# 01_Structure.net
KiCad netlist of a schematic drawn in Altium Designer
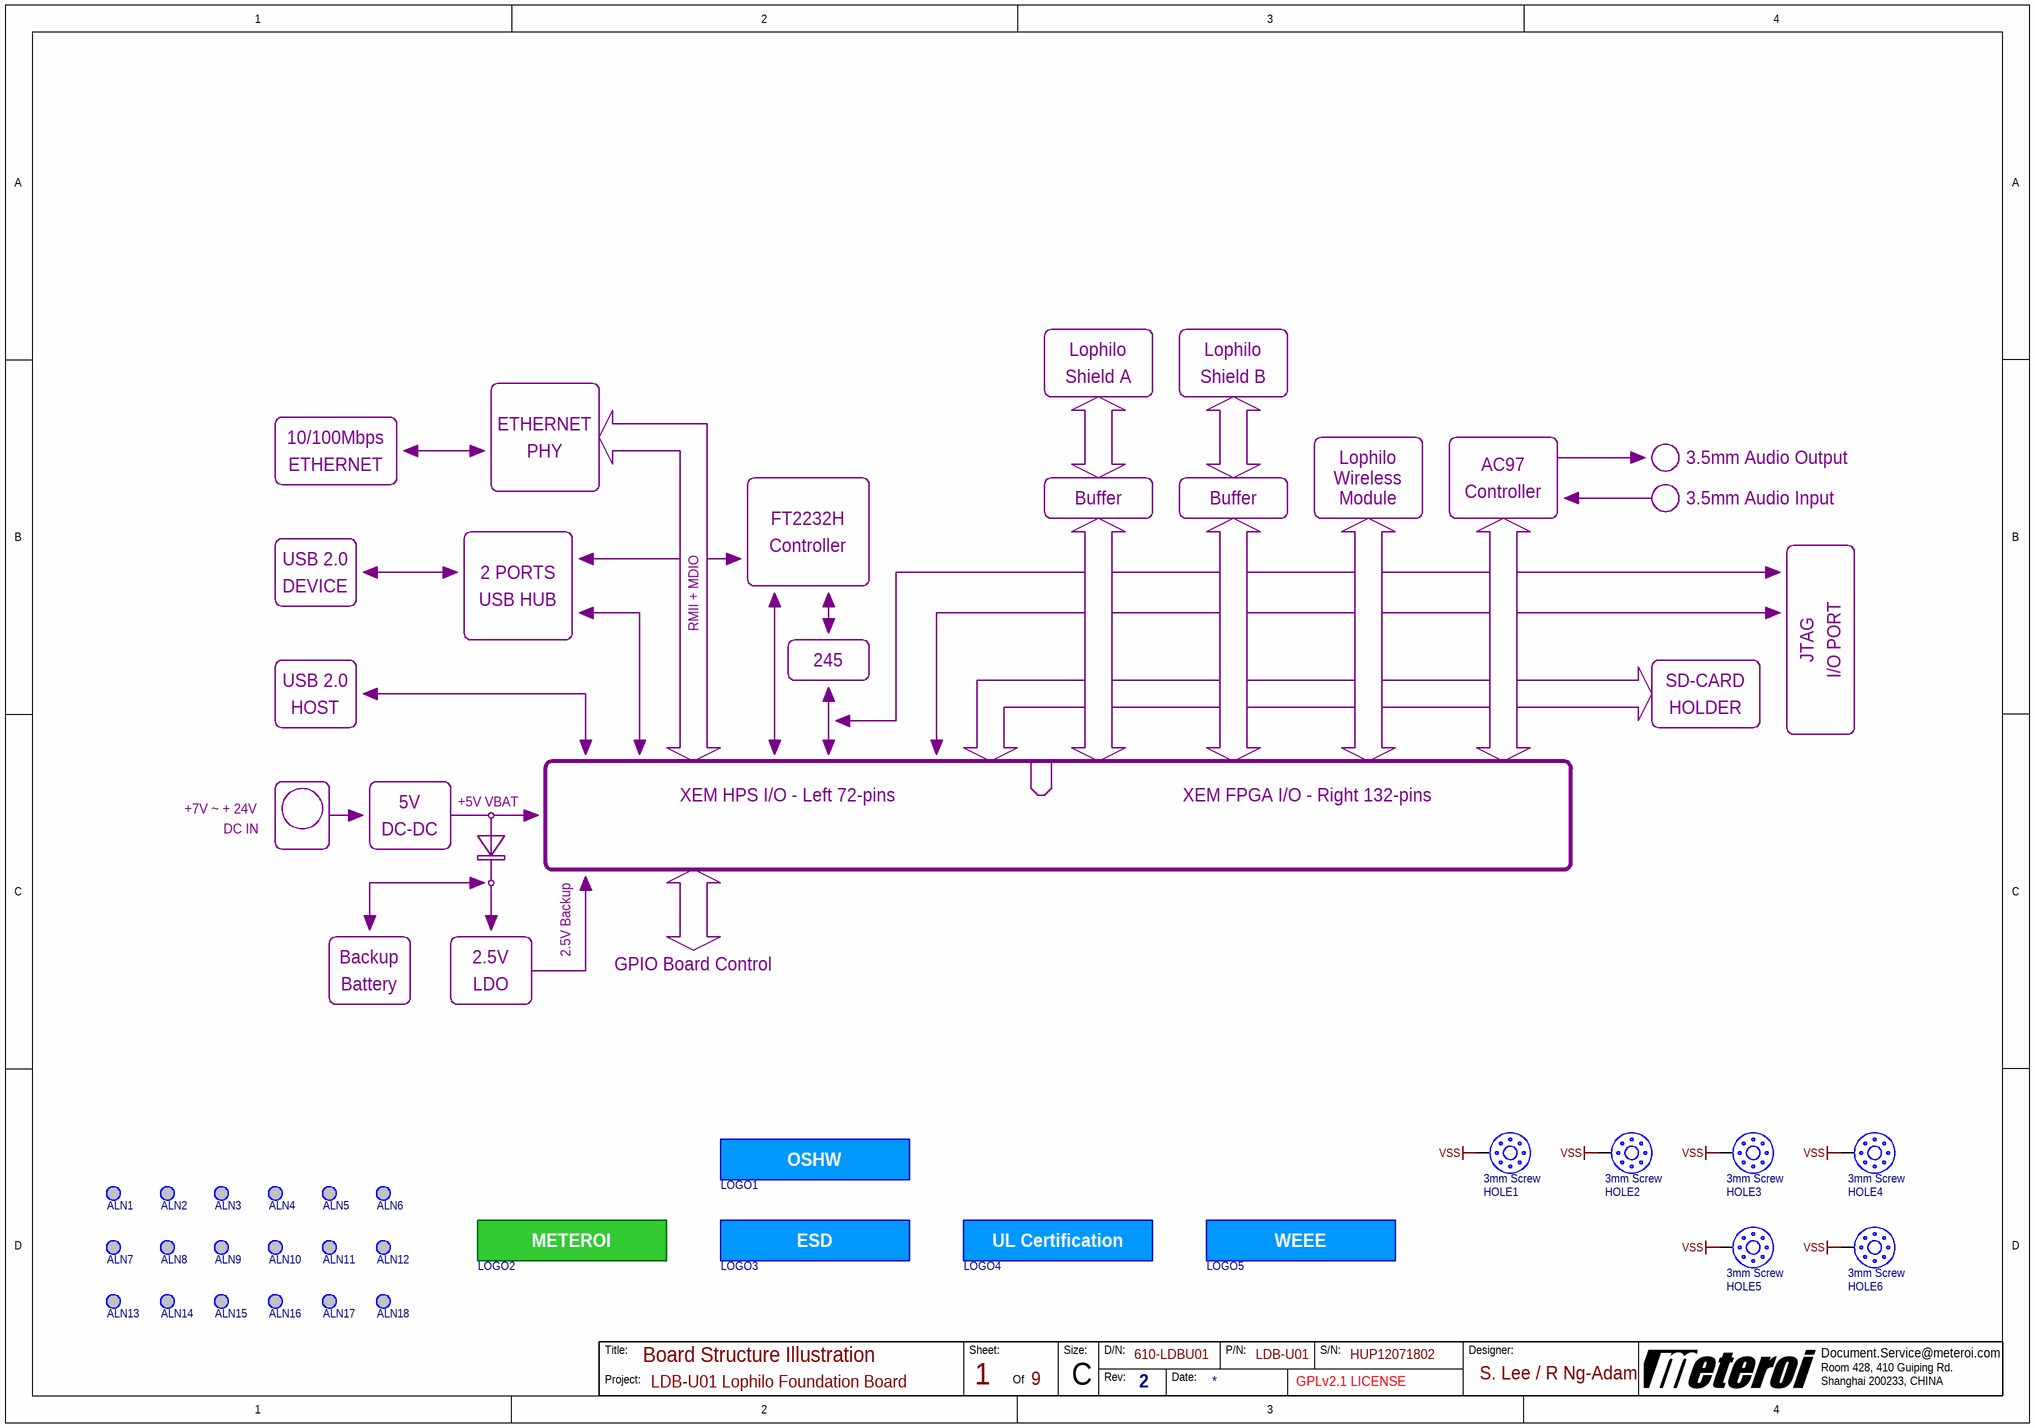
[diagram p0: 01_Structure.SchDoc]

(export (version "E")
  (design (tool "Eeschema 10.0.6"))
  (components
    (comp (ref "ALN1")
      (value "Assembly Optical Align")
      (footprint "ALIGN_1")
      (fields
        (field (name "PARTNUMBER") "0")
        (field (name "PUBLISHER") "Cowin")
        (field (name "DESIGNER") "shyul")
      )
      (libsource (lib "PCBElement_Manufacture") (part "ALIGN"))
    )
    (comp (ref "ALN2")
      (value "Assembly Optical Align")
      (footprint "ALIGN_1")
      (fields
        (field (name "PARTNUMBER") "0")
        (field (name "PUBLISHER") "Cowin")
        (field (name "DESIGNER") "shyul")
      )
      (libsource (lib "PCBElement_Manufacture") (part "ALIGN"))
    )
    (comp (ref "ALN3")
      (value "Assembly Optical Align")
      (footprint "ALIGN_1")
      (fields
        (field (name "PARTNUMBER") "0")
        (field (name "PUBLISHER") "Cowin")
        (field (name "DESIGNER") "shyul")
      )
      (libsource (lib "PCBElement_Manufacture") (part "ALIGN"))
    )
    (comp (ref "ALN4")
      (value "Assembly Optical Align")
      (footprint "ALIGN_1")
      (fields
        (field (name "PARTNUMBER") "0")
        (field (name "PUBLISHER") "Cowin")
        (field (name "DESIGNER") "shyul")
      )
      (libsource (lib "PCBElement_Manufacture") (part "ALIGN"))
    )
    (comp (ref "ALN5")
      (value "Assembly Optical Align")
      (footprint "ALIGN_1")
      (fields
        (field (name "PARTNUMBER") "0")
        (field (name "PUBLISHER") "Cowin")
        (field (name "DESIGNER") "shyul")
      )
      (libsource (lib "PCBElement_Manufacture") (part "ALIGN"))
    )
    (comp (ref "ALN6")
      (value "Assembly Optical Align")
      (footprint "ALIGN_1")
      (fields
        (field (name "PARTNUMBER") "0")
        (field (name "PUBLISHER") "Cowin")
        (field (name "DESIGNER") "shyul")
      )
      (libsource (lib "PCBElement_Manufacture") (part "ALIGN"))
    )
    (comp (ref "ALN7")
      (value "Assembly Optical Align")
      (footprint "ALIGN_1")
      (fields
        (field (name "PARTNUMBER") "0")
        (field (name "PUBLISHER") "Cowin")
        (field (name "DESIGNER") "shyul")
      )
      (libsource (lib "PCBElement_Manufacture") (part "ALIGN"))
    )
    (comp (ref "ALN8")
      (value "Assembly Optical Align")
      (footprint "ALIGN_1")
      (fields
        (field (name "PARTNUMBER") "0")
        (field (name "PUBLISHER") "Cowin")
        (field (name "DESIGNER") "shyul")
      )
      (libsource (lib "PCBElement_Manufacture") (part "ALIGN"))
    )
    (comp (ref "ALN9")
      (value "Assembly Optical Align")
      (footprint "ALIGN_1")
      (fields
        (field (name "PARTNUMBER") "0")
        (field (name "PUBLISHER") "Cowin")
        (field (name "DESIGNER") "shyul")
      )
      (libsource (lib "PCBElement_Manufacture") (part "ALIGN"))
    )
    (comp (ref "ALN10")
      (value "Assembly Optical Align")
      (footprint "ALIGN_1")
      (fields
        (field (name "PARTNUMBER") "0")
        (field (name "PUBLISHER") "Cowin")
        (field (name "DESIGNER") "shyul")
      )
      (libsource (lib "PCBElement_Manufacture") (part "ALIGN"))
    )
    (comp (ref "ALN11")
      (value "Assembly Optical Align")
      (footprint "ALIGN_1")
      (fields
        (field (name "PARTNUMBER") "0")
        (field (name "PUBLISHER") "Cowin")
        (field (name "DESIGNER") "shyul")
      )
      (libsource (lib "PCBElement_Manufacture") (part "ALIGN"))
    )
    (comp (ref "ALN12")
      (value "Assembly Optical Align")
      (footprint "ALIGN_1")
      (fields
        (field (name "PARTNUMBER") "0")
        (field (name "PUBLISHER") "Cowin")
        (field (name "DESIGNER") "shyul")
      )
      (libsource (lib "PCBElement_Manufacture") (part "ALIGN"))
    )
    (comp (ref "ALN13")
      (value "Assembly Optical Align")
      (footprint "ALIGN_1")
      (fields
        (field (name "PARTNUMBER") "0")
        (field (name "PUBLISHER") "Cowin")
        (field (name "DESIGNER") "shyul")
      )
      (libsource (lib "PCBElement_Manufacture") (part "ALIGN"))
    )
    (comp (ref "ALN14")
      (value "Assembly Optical Align")
      (footprint "ALIGN_1")
      (fields
        (field (name "PARTNUMBER") "0")
        (field (name "PUBLISHER") "Cowin")
        (field (name "DESIGNER") "shyul")
      )
      (libsource (lib "PCBElement_Manufacture") (part "ALIGN"))
    )
    (comp (ref "ALN15")
      (value "Assembly Optical Align")
      (footprint "ALIGN_1")
      (fields
        (field (name "PARTNUMBER") "0")
        (field (name "PUBLISHER") "Cowin")
        (field (name "DESIGNER") "shyul")
      )
      (libsource (lib "PCBElement_Manufacture") (part "ALIGN"))
    )
    (comp (ref "ALN16")
      (value "Assembly Optical Align")
      (footprint "ALIGN_1")
      (fields
        (field (name "PARTNUMBER") "0")
        (field (name "PUBLISHER") "Cowin")
        (field (name "DESIGNER") "shyul")
      )
      (libsource (lib "PCBElement_Manufacture") (part "ALIGN"))
    )
    (comp (ref "ALN17")
      (value "Assembly Optical Align")
      (footprint "ALIGN_1")
      (fields
        (field (name "PARTNUMBER") "0")
        (field (name "PUBLISHER") "Cowin")
        (field (name "DESIGNER") "shyul")
      )
      (libsource (lib "PCBElement_Manufacture") (part "ALIGN"))
    )
    (comp (ref "ALN18")
      (value "Assembly Optical Align")
      (footprint "ALIGN_1")
      (fields
        (field (name "PARTNUMBER") "0")
        (field (name "PUBLISHER") "Cowin")
        (field (name "DESIGNER") "shyul")
      )
      (libsource (lib "PCBElement_Manufacture") (part "ALIGN"))
    )
    (comp (ref "HOLE1")
      (value "3mm Screw")
      (footprint "HOLE_3_S")
      (description "PCB hole for screw installations")
      (fields
        (field (name "PARTNUMBER") "0")
        (field (name "PUBLISHER") "Cowin")
        (field (name "DESIGNER") "shyul")
      )
      (libsource (lib "PCBElement_Manufacture") (part "HOLE"))
    )
    (comp (ref "HOLE2")
      (value "3mm Screw")
      (footprint "HOLE_3_S")
      (description "PCB hole for screw installations")
      (fields
        (field (name "PARTNUMBER") "0")
        (field (name "PUBLISHER") "Cowin")
        (field (name "DESIGNER") "shyul")
      )
      (libsource (lib "PCBElement_Manufacture") (part "HOLE"))
    )
    (comp (ref "HOLE3")
      (value "3mm Screw")
      (footprint "HOLE_3_S")
      (description "PCB hole for screw installations")
      (fields
        (field (name "PARTNUMBER") "0")
        (field (name "PUBLISHER") "Cowin")
        (field (name "DESIGNER") "shyul")
      )
      (libsource (lib "PCBElement_Manufacture") (part "HOLE"))
    )
    (comp (ref "HOLE4")
      (value "3mm Screw")
      (footprint "HOLE_3_S")
      (description "PCB hole for screw installations")
      (fields
        (field (name "PARTNUMBER") "0")
        (field (name "PUBLISHER") "Cowin")
        (field (name "DESIGNER") "shyul")
      )
      (libsource (lib "PCBElement_Manufacture") (part "HOLE"))
    )
    (comp (ref "HOLE5")
      (value "3mm Screw")
      (footprint "HOLE_3_S")
      (description "PCB hole for screw installations")
      (fields
        (field (name "PARTNUMBER") "0")
        (field (name "PUBLISHER") "Cowin")
        (field (name "DESIGNER") "shyul")
      )
      (libsource (lib "PCBElement_Manufacture") (part "HOLE"))
    )
    (comp (ref "HOLE6")
      (value "3mm Screw")
      (footprint "HOLE_3_S")
      (description "PCB hole for screw installations")
      (fields
        (field (name "PARTNUMBER") "0")
        (field (name "PUBLISHER") "Cowin")
        (field (name "DESIGNER") "shyul")
      )
      (libsource (lib "PCBElement_Manufacture") (part "HOLE"))
    )
    (comp (ref "LOGO1")
      (value "OSHW")
      (footprint "LOGO_OSHW_2")
      (description "OSHW Logo")
      (fields
        (field (name "PARTNUMBER") "0")
        (field (name "PUBLISHER") "Cowin")
        (field (name "DESIGNER") "shyul")
      )
      (libsource (lib "PCBElement_Logo") (part "REGULATION_OSHW"))
    )
    (comp (ref "LOGO2")
      (value "LOGO")
      (footprint "LOGO_METEROI_ST_12X3")
      (description "Meteroi Logo")
      (fields
        (field (name "PARTNUMBER") "0")
        (field (name "PUBLISHER") "Cowin")
        (field (name "DESIGNER") "shyul")
      )
      (libsource (lib "PCBElement_Logo") (part "LOGO_METEROI"))
    )
    (comp (ref "LOGO3")
      (value "ESD")
      (footprint "REGULATION_ESD")
      (description "ESD Logo")
      (fields
        (field (name "PARTNUMBER") "0")
        (field (name "PUBLISHER") "Cowin")
        (field (name "DESIGNER") "shyul")
      )
      (libsource (lib "PCBElement_Logo") (part "REGULATION_ESD"))
    )
    (comp (ref "LOGO4")
      (value "UL Certification")
      (footprint "REGULATION_PCB_UL")
      (description "PCB UL Certification")
      (fields
        (field (name "PARTNUMBER") "0")
        (field (name "PUBLISHER") "Cowin")
        (field (name "DESIGNER") "shyul")
      )
      (libsource (lib "PCBElement_Logo") (part "REGULATION_PCB_UL"))
    )
    (comp (ref "LOGO5")
      (value "WEEE")
      (footprint "REGULATION_WEEE")
      (description "WEEE Logo")
      (fields
        (field (name "PARTNUMBER") "0")
        (field (name "PUBLISHER") "Cowin")
        (field (name "DESIGNER") "shyul")
      )
      (libsource (lib "PCBElement_Logo") (part "REGULATION_WEEE"))
    )
  )
  (nets
    (net (code "1") (name "VSS") (class "Default")
      (node (ref "HOLE1") (pin "1") (pinfunction "GND_1") (pintype "passive"))
      (node (ref "HOLE2") (pin "1") (pinfunction "GND_1") (pintype "passive"))
      (node (ref "HOLE3") (pin "1") (pinfunction "GND_1") (pintype "passive"))
      (node (ref "HOLE4") (pin "1") (pinfunction "GND_1") (pintype "passive"))
      (node (ref "HOLE5") (pin "1") (pinfunction "GND_1") (pintype "passive"))
      (node (ref "HOLE6") (pin "1") (pinfunction "GND_1") (pintype "passive"))
    )
  )
)
